# Adafrruit_Bluefruit_LE_USB_Friend_CP2102.net
KiCad netlist of a schematic drawn in EAGLE
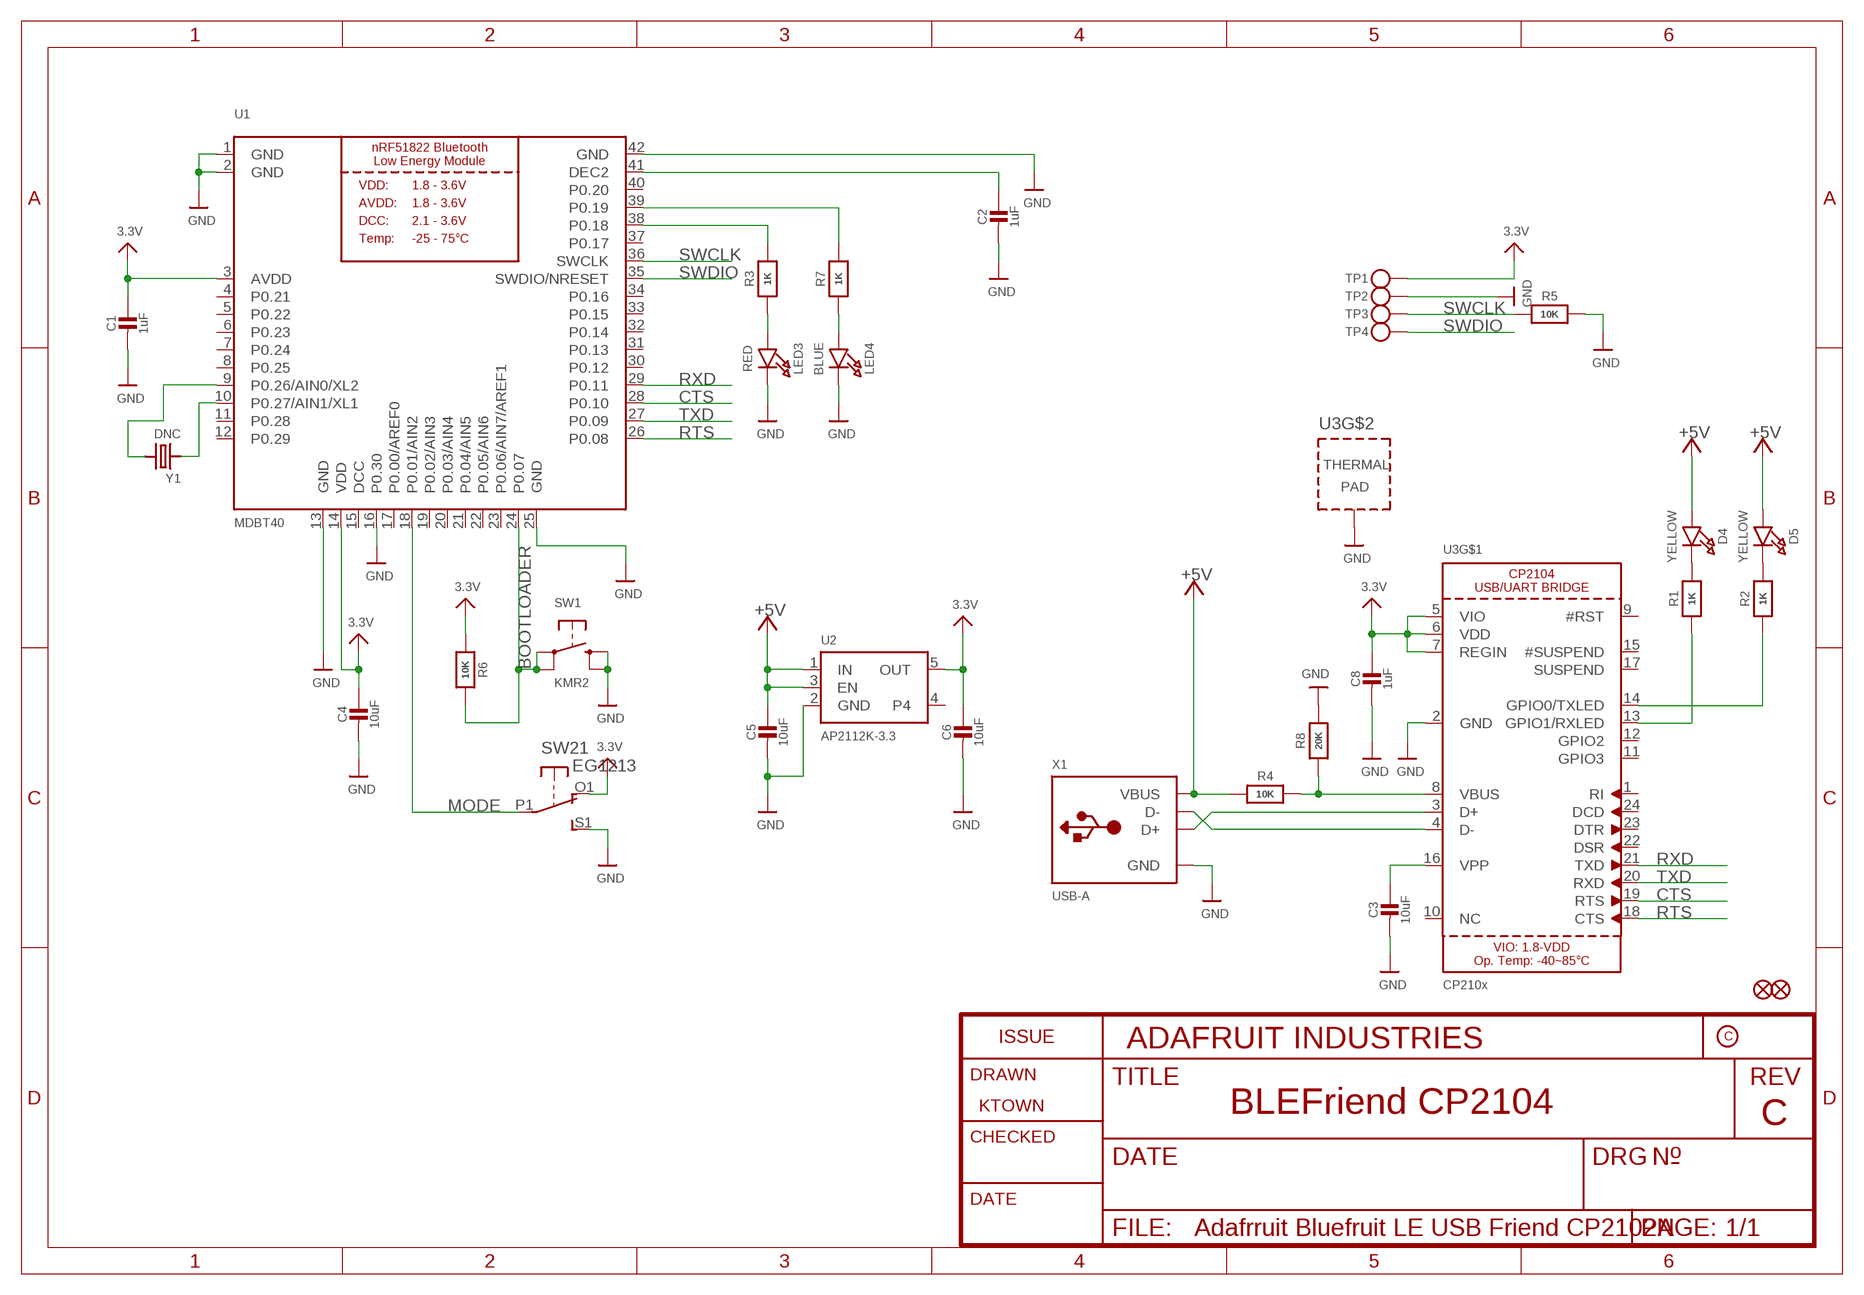
[diagram p0: schematic, sheet 1]

(export (version "E")
  (design (tool "Eeschema 10.0.6"))
  (components
    (comp (ref "C1")
      (value "1uF")
      (footprint "eagle-import:0603-NO")
      (libsource (lib "eagle-import") (part "CAP_CERAMIC0603_NO"))
    )
    (comp (ref "C2")
      (value "1uF")
      (footprint "eagle-import:0603-NO")
      (libsource (lib "eagle-import") (part "CAP_CERAMIC0603_NO"))
    )
    (comp (ref "C3")
      (value "10uF")
      (footprint "eagle-import:0805-NO")
      (libsource (lib "eagle-import") (part "CAP_CERAMIC0805-NOOUTLINE"))
    )
    (comp (ref "C4")
      (value "10uF")
      (footprint "eagle-import:0805-NO")
      (libsource (lib "eagle-import") (part "CAP_CERAMIC0805-NOOUTLINE"))
    )
    (comp (ref "C5")
      (value "10uF")
      (footprint "eagle-import:0805-NO")
      (libsource (lib "eagle-import") (part "CAP_CERAMIC0805-NOOUTLINE"))
    )
    (comp (ref "C6")
      (value "10uF")
      (footprint "eagle-import:0805-NO")
      (libsource (lib "eagle-import") (part "CAP_CERAMIC0805-NOOUTLINE"))
    )
    (comp (ref "C8")
      (value "1uF")
      (footprint "eagle-import:0603-NO")
      (libsource (lib "eagle-import") (part "CAP_CERAMIC0603_NO"))
    )
    (comp (ref "D4")
      (value "YELLOW")
      (footprint "eagle-import:CHIPLED_0805_NOOUTLINE")
      (libsource (lib "eagle-import") (part "LED0805_NOOUTLINE"))
    )
    (comp (ref "D5")
      (value "YELLOW")
      (footprint "eagle-import:CHIPLED_0805_NOOUTLINE")
      (libsource (lib "eagle-import") (part "LED0805_NOOUTLINE"))
    )
    (comp (ref "FID1")
      (value "FIDUCIAL_1MM")
      (footprint "eagle-import:FIDUCIAL_1MM")
      (libsource (lib "eagle-import") (part "FIDUCIAL_1MM"))
    )
    (comp (ref "FID2")
      (value "FIDUCIAL_1MM")
      (footprint "eagle-import:FIDUCIAL_1MM")
      (libsource (lib "eagle-import") (part "FIDUCIAL_1MM"))
    )
    (comp (ref "LED3")
      (value "RED")
      (footprint "eagle-import:CHIPLED_0805_NOOUTLINE")
      (libsource (lib "eagle-import") (part "LED0805_NOOUTLINE"))
    )
    (comp (ref "LED4")
      (value "BLUE")
      (footprint "eagle-import:CHIPLED_0805_NOOUTLINE")
      (libsource (lib "eagle-import") (part "LED0805_NOOUTLINE"))
    )
    (comp (ref "R1")
      (value "1K")
      (footprint "eagle-import:0603-NO")
      (libsource (lib "eagle-import") (part "RESISTOR_0603_NOOUT"))
    )
    (comp (ref "R2")
      (value "1K")
      (footprint "eagle-import:0603-NO")
      (libsource (lib "eagle-import") (part "RESISTOR_0603_NOOUT"))
    )
    (comp (ref "R3")
      (value "1K")
      (footprint "eagle-import:0603-NO")
      (libsource (lib "eagle-import") (part "RESISTOR_0603_NOOUT"))
    )
    (comp (ref "R4")
      (value "10K")
      (footprint "eagle-import:0603-NO")
      (libsource (lib "eagle-import") (part "RESISTOR_0603_NOOUT"))
    )
    (comp (ref "R5")
      (value "10K")
      (footprint "eagle-import:0603-NO")
      (libsource (lib "eagle-import") (part "RESISTOR_0603_NOOUT"))
    )
    (comp (ref "R6")
      (value "10K")
      (footprint "eagle-import:0603-NO")
      (libsource (lib "eagle-import") (part "RESISTOR_0603_NOOUT"))
    )
    (comp (ref "R7")
      (value "1K")
      (footprint "eagle-import:0603-NO")
      (libsource (lib "eagle-import") (part "RESISTOR_0603_NOOUT"))
    )
    (comp (ref "R8")
      (value "20K")
      (footprint "eagle-import:0603-NO")
      (libsource (lib "eagle-import") (part "RESISTOR_0603_NOOUT"))
    )
    (comp (ref "SW1")
      (value "KMR2")
      (footprint "eagle-import:BTN_KMR2_4.6X2.8")
      (libsource (lib "eagle-import") (part "SWITCH_TACT_SMT4.6X2.8"))
    )
    (comp (ref "SW2")
      (value "EG1213")
      (footprint "eagle-import:EG1390")
      (libsource (lib "eagle-import") (part "DPDT-EG1390"))
    )
    (comp (ref "TP1")
      (value "TESTPOINTROUND2MM")
      (footprint "eagle-import:TESTPOINT_ROUND_2MM")
      (libsource (lib "eagle-import") (part "TESTPOINTROUND2MM"))
    )
    (comp (ref "TP2")
      (value "TESTPOINTROUND2MM")
      (footprint "eagle-import:TESTPOINT_ROUND_2MM")
      (libsource (lib "eagle-import") (part "TESTPOINTROUND2MM"))
    )
    (comp (ref "TP3")
      (value "TESTPOINTROUND2MM")
      (footprint "eagle-import:TESTPOINT_ROUND_2MM")
      (libsource (lib "eagle-import") (part "TESTPOINTROUND2MM"))
    )
    (comp (ref "TP4")
      (value "TESTPOINTROUND2MM")
      (footprint "eagle-import:TESTPOINT_ROUND_2MM")
      (libsource (lib "eagle-import") (part "TESTPOINTROUND2MM"))
    )
    (comp (ref "U1")
      (value "MDBT40")
      (footprint "eagle-import:BLE_MODULE_RAYTAC_MDBT40")
      (libsource (lib "eagle-import") (part "NRF51822_MODULE_MDBT40"))
    )
    (comp (ref "U2")
      (value "AP2112K-3.3")
      (footprint "eagle-import:SOT23-5")
      (libsource (lib "eagle-import") (part "VREG_SOT23-5"))
    )
    (comp (ref "U3")
      (value "CP210x")
      (footprint "eagle-import:QFN24_4MM_SMSC")
      (libsource (lib "eagle-import") (part "CP2104"))
    )
    (comp (ref "X1")
      (value "USB-A")
      (footprint "eagle-import:USB_A-THM")
      (libsource (lib "eagle-import") (part "USB_TYPEA_CLIENTTHM"))
    )
    (comp (ref "Y1")
      (value "DNC")
      (footprint "eagle-import:CRYSTAL_CYL_2X6MM_SMT")
      (libsource (lib "eagle-import") (part "CRYSTAL2.0X6.0_32.768"))
    )
  )
  (nets
    (net (code "1") (name "+5V") (class "Default")
      (node (ref "C5") (pin "1") (pinfunction "1_1") (pintype "passive"))
      (node (ref "D4") (pin "A") (pinfunction "A_A") (pintype "passive"))
      (node (ref "D5") (pin "A") (pinfunction "A_A") (pintype "passive"))
      (node (ref "R4") (pin "1") (pinfunction "1_1") (pintype "passive"))
      (node (ref "U2") (pin "1") (pinfunction "IN_1") (pintype "power_in"))
      (node (ref "U2") (pin "3") (pinfunction "EN_3") (pintype "input"))
      (node (ref "X1") (pin "VBUS") (pinfunction "VBUS_VBUS") (pintype "power_in"))
    )
    (net (code "2") (name "/BOOTLOADER") (class "Default")
      (node (ref "R6") (pin "2") (pinfunction "2_2") (pintype "passive"))
      (node (ref "SW1") (pin "A") (pinfunction "P_A") (pintype "passive"))
      (node (ref "SW1") (pin "A'") (pinfunction "P1_A'") (pintype "passive"))
      (node (ref "U1") (pin "24") (pinfunction "P0.07_24") (pintype "bidirectional"))
    )
    (net (code "3") (name "/CTS") (class "Default")
      (node (ref "U1") (pin "28") (pinfunction "P0.10_28") (pintype "bidirectional"))
      (node (ref "U3") (pin "19") (pinfunction "RTS_19") (pintype "output"))
    )
    (net (code "4") (name "/DCC") (class "Default")
      (node (ref "U1") (pin "15") (pinfunction "DCC_15") (pintype "power_in"))
    )
    (net (code "5") (name "/MODE") (class "Default")
      (node (ref "SW2") (pin "P1") (pinfunction "P_P1") (pintype "passive"))
      (node (ref "U1") (pin "18") (pinfunction "P0.01/AIN2_18") (pintype "bidirectional"))
    )
    (net (code "6") (name "/RTS") (class "Default")
      (node (ref "U1") (pin "26") (pinfunction "P0.08_26") (pintype "bidirectional"))
      (node (ref "U3") (pin "18") (pinfunction "CTS_18") (pintype "input"))
    )
    (net (code "7") (name "/RXD") (class "Default")
      (node (ref "U1") (pin "29") (pinfunction "P0.11_29") (pintype "bidirectional"))
      (node (ref "U3") (pin "21") (pinfunction "TXD_21") (pintype "output"))
    )
    (net (code "8") (name "/SWCLK") (class "Default")
      (node (ref "R5") (pin "1") (pinfunction "1_1") (pintype "passive"))
      (node (ref "TP3") (pin "P$1") (pinfunction "P$1_P$1") (pintype "bidirectional"))
      (node (ref "U1") (pin "36") (pinfunction "SWCLK_36") (pintype "bidirectional"))
    )
    (net (code "9") (name "/SWDIO") (class "Default")
      (node (ref "TP4") (pin "P$1") (pinfunction "P$1_P$1") (pintype "bidirectional"))
      (node (ref "U1") (pin "35") (pinfunction "SWDIO/NRESET_35") (pintype "bidirectional"))
    )
    (net (code "10") (name "/TXD") (class "Default")
      (node (ref "U1") (pin "27") (pinfunction "P0.09_27") (pintype "bidirectional"))
      (node (ref "U3") (pin "20") (pinfunction "RXD_20") (pintype "input"))
    )
    (net (code "11") (name "3.3V") (class "Default")
      (node (ref "C1") (pin "1") (pinfunction "1_1") (pintype "passive"))
      (node (ref "C4") (pin "1") (pinfunction "1_1") (pintype "passive"))
      (node (ref "C6") (pin "1") (pinfunction "1_1") (pintype "passive"))
      (node (ref "C8") (pin "1") (pinfunction "1_1") (pintype "passive"))
      (node (ref "R6") (pin "1") (pinfunction "1_1") (pintype "passive"))
      (node (ref "SW2") (pin "O1") (pinfunction "O_O1") (pintype "passive"))
      (node (ref "TP1") (pin "P$1") (pinfunction "P$1_P$1") (pintype "bidirectional"))
      (node (ref "U1") (pin "14") (pinfunction "VDD_14") (pintype "power_in"))
      (node (ref "U1") (pin "3") (pinfunction "AVDD_3") (pintype "power_in"))
      (node (ref "U2") (pin "5") (pinfunction "OUT_5") (pintype "power_in"))
      (node (ref "U3") (pin "5") (pinfunction "VIO_5") (pintype "power_in"))
      (node (ref "U3") (pin "6") (pinfunction "VDD_6") (pintype "power_in"))
      (node (ref "U3") (pin "7") (pinfunction "REGIN_7") (pintype "power_in"))
    )
    (net (code "12") (name "GND") (class "Default")
      (node (ref "C1") (pin "2") (pinfunction "2_2") (pintype "passive"))
      (node (ref "C2") (pin "2") (pinfunction "2_2") (pintype "passive"))
      (node (ref "C3") (pin "2") (pinfunction "2_2") (pintype "passive"))
      (node (ref "C4") (pin "2") (pinfunction "2_2") (pintype "passive"))
      (node (ref "C5") (pin "2") (pinfunction "2_2") (pintype "passive"))
      (node (ref "C6") (pin "2") (pinfunction "2_2") (pintype "passive"))
      (node (ref "C8") (pin "2") (pinfunction "2_2") (pintype "passive"))
      (node (ref "LED3") (pin "C") (pinfunction "C_C") (pintype "passive"))
      (node (ref "LED4") (pin "C") (pinfunction "C_C") (pintype "passive"))
      (node (ref "R5") (pin "2") (pinfunction "2_2") (pintype "passive"))
      (node (ref "R8") (pin "2") (pinfunction "2_2") (pintype "passive"))
      (node (ref "SW1") (pin "B") (pinfunction "S_B") (pintype "passive"))
      (node (ref "SW1") (pin "B'") (pinfunction "S1_B'") (pintype "passive"))
      (node (ref "SW2") (pin "S1") (pinfunction "S_S1") (pintype "passive"))
      (node (ref "TP2") (pin "P$1") (pinfunction "P$1_P$1") (pintype "bidirectional"))
      (node (ref "U1") (pin "1") (pinfunction "GND_1") (pintype "power_in"))
      (node (ref "U1") (pin "13") (pinfunction "GND_13") (pintype "power_in"))
      (node (ref "U1") (pin "16") (pinfunction "P0.30_16") (pintype "bidirectional"))
      (node (ref "U1") (pin "2") (pinfunction "GND_2") (pintype "power_in"))
      (node (ref "U1") (pin "25") (pinfunction "GND_25") (pintype "power_in"))
      (node (ref "U1") (pin "42") (pinfunction "GND_42") (pintype "power_in"))
      (node (ref "U2") (pin "2") (pinfunction "GND_2") (pintype "power_in"))
      (node (ref "U3") (pin "2") (pinfunction "GND_2") (pintype "power_in"))
      (node (ref "U3") (pin "THERM") (pinfunction "TP_THERM") (pintype "power_in"))
      (node (ref "X1") (pin "GND") (pinfunction "GND_GND") (pintype "power_in"))
    )
    (net (code "13") (name "Net-(D4-PadC)") (class "Default")
      (node (ref "D4") (pin "C") (pinfunction "C_C") (pintype "passive"))
      (node (ref "R1") (pin "2") (pinfunction "2_2") (pintype "passive"))
    )
    (net (code "14") (name "Net-(D5-PadC)") (class "Default")
      (node (ref "D5") (pin "C") (pinfunction "C_C") (pintype "passive"))
      (node (ref "R2") (pin "2") (pinfunction "2_2") (pintype "passive"))
    )
    (net (code "15") (name "Net-(LED3-PadA)") (class "Default")
      (node (ref "LED3") (pin "A") (pinfunction "A_A") (pintype "passive"))
      (node (ref "R3") (pin "1") (pinfunction "1_1") (pintype "passive"))
    )
    (net (code "16") (name "Net-(LED4-PadA)") (class "Default")
      (node (ref "LED4") (pin "A") (pinfunction "A_A") (pintype "passive"))
      (node (ref "R7") (pin "1") (pinfunction "1_1") (pintype "passive"))
    )
    (net (code "17") (name "Net-(U1-DEC2)") (class "Default")
      (node (ref "C2") (pin "1") (pinfunction "1_1") (pintype "passive"))
      (node (ref "U1") (pin "41") (pinfunction "DEC2_41") (pintype "power_in"))
    )
    (net (code "18") (name "Net-(U1-P0.18)") (class "Default")
      (node (ref "R3") (pin "2") (pinfunction "2_2") (pintype "passive"))
      (node (ref "U1") (pin "38") (pinfunction "P0.18_38") (pintype "bidirectional"))
    )
    (net (code "19") (name "Net-(U1-P0.19)") (class "Default")
      (node (ref "R7") (pin "2") (pinfunction "2_2") (pintype "passive"))
      (node (ref "U1") (pin "39") (pinfunction "P0.19_39") (pintype "bidirectional"))
    )
    (net (code "20") (name "Net-(U1-P0.26{slash}AIN0{slash}XL2)") (class "Default")
      (node (ref "U1") (pin "9") (pinfunction "P0.26/AIN0/XL2_9") (pintype "bidirectional"))
      (node (ref "Y1") (pin "2") (pinfunction "2_2") (pintype "passive"))
    )
    (net (code "21") (name "Net-(U1-P0.27{slash}AIN1{slash}XL1)") (class "Default")
      (node (ref "U1") (pin "10") (pinfunction "P0.27/AIN1/XL1_10") (pintype "bidirectional"))
      (node (ref "Y1") (pin "1") (pinfunction "1_1") (pintype "passive"))
    )
    (net (code "22") (name "Net-(U3A-D+)") (class "Default")
      (node (ref "U3") (pin "3") (pinfunction "D+_3") (pintype "bidirectional"))
      (node (ref "X1") (pin "D+") (pinfunction "D+_D+") (pintype "bidirectional"))
    )
    (net (code "23") (name "Net-(U3A-D-)") (class "Default")
      (node (ref "U3") (pin "4") (pinfunction "D-_4") (pintype "bidirectional"))
      (node (ref "X1") (pin "D-") (pinfunction "D-_D-") (pintype "bidirectional"))
    )
    (net (code "24") (name "Net-(U3A-GPIO0{slash}TXLED)") (class "Default")
      (node (ref "R2") (pin "1") (pinfunction "1_1") (pintype "passive"))
      (node (ref "U3") (pin "14") (pinfunction "GPIO0/TXLED_14") (pintype "bidirectional"))
    )
    (net (code "25") (name "Net-(U3A-GPIO1{slash}RXLED)") (class "Default")
      (node (ref "R1") (pin "1") (pinfunction "1_1") (pintype "passive"))
      (node (ref "U3") (pin "13") (pinfunction "GPIO1/RXLED_13") (pintype "bidirectional"))
    )
    (net (code "26") (name "Net-(U3A-VBUS)") (class "Default")
      (node (ref "R4") (pin "2") (pinfunction "2_2") (pintype "passive"))
      (node (ref "R8") (pin "1") (pinfunction "1_1") (pintype "passive"))
      (node (ref "U3") (pin "8") (pinfunction "VBUS_8") (pintype "power_in"))
    )
    (net (code "27") (name "Net-(U3A-VPP)") (class "Default")
      (node (ref "C3") (pin "1") (pinfunction "1_1") (pintype "passive"))
      (node (ref "U3") (pin "16") (pinfunction "VPP_16") (pintype "bidirectional"))
    )
    (net (code "28") (name "unconnected-(U1-P0.00{slash}AREF0-Pad17)") (class "Default")
      (node (ref "U1") (pin "17") (pinfunction "P0.00/AREF0_17") (pintype "bidirectional"))
    )
    (net (code "29") (name "unconnected-(U1-P0.02{slash}AIN3-Pad19)") (class "Default")
      (node (ref "U1") (pin "19") (pinfunction "P0.02/AIN3_19") (pintype "bidirectional"))
    )
    (net (code "30") (name "unconnected-(U1-P0.03{slash}AIN4-Pad20)") (class "Default")
      (node (ref "U1") (pin "20") (pinfunction "P0.03/AIN4_20") (pintype "bidirectional"))
    )
    (net (code "31") (name "unconnected-(U1-P0.04{slash}AIN5-Pad21)") (class "Default")
      (node (ref "U1") (pin "21") (pinfunction "P0.04/AIN5_21") (pintype "bidirectional"))
    )
    (net (code "32") (name "unconnected-(U1-P0.05{slash}AIN6-Pad22)") (class "Default")
      (node (ref "U1") (pin "22") (pinfunction "P0.05/AIN6_22") (pintype "bidirectional"))
    )
    (net (code "33") (name "unconnected-(U1-P0.06{slash}AIN7{slash}AREF1-Pad23)") (class "Default")
      (node (ref "U1") (pin "23") (pinfunction "P0.06/AIN7/AREF1_23") (pintype "bidirectional"))
    )
    (net (code "34") (name "unconnected-(U1-P0.12-Pad30)") (class "Default")
      (node (ref "U1") (pin "30") (pinfunction "P0.12_30") (pintype "bidirectional"))
    )
    (net (code "35") (name "unconnected-(U1-P0.13-Pad31)") (class "Default")
      (node (ref "U1") (pin "31") (pinfunction "P0.13_31") (pintype "bidirectional"))
    )
    (net (code "36") (name "unconnected-(U1-P0.14-Pad32)") (class "Default")
      (node (ref "U1") (pin "32") (pinfunction "P0.14_32") (pintype "bidirectional"))
    )
    (net (code "37") (name "unconnected-(U1-P0.15-Pad33)") (class "Default")
      (node (ref "U1") (pin "33") (pinfunction "P0.15_33") (pintype "bidirectional"))
    )
    (net (code "38") (name "unconnected-(U1-P0.16-Pad34)") (class "Default")
      (node (ref "U1") (pin "34") (pinfunction "P0.16_34") (pintype "bidirectional"))
    )
    (net (code "39") (name "unconnected-(U1-P0.17-Pad37)") (class "Default")
      (node (ref "U1") (pin "37") (pinfunction "P0.17_37") (pintype "bidirectional"))
    )
    (net (code "40") (name "unconnected-(U1-P0.20-Pad40)") (class "Default")
      (node (ref "U1") (pin "40") (pinfunction "P0.20_40") (pintype "bidirectional"))
    )
    (net (code "41") (name "unconnected-(U1-P0.21-Pad4)") (class "Default")
      (node (ref "U1") (pin "4") (pinfunction "P0.21_4") (pintype "bidirectional"))
    )
    (net (code "42") (name "unconnected-(U1-P0.22-Pad5)") (class "Default")
      (node (ref "U1") (pin "5") (pinfunction "P0.22_5") (pintype "bidirectional"))
    )
    (net (code "43") (name "unconnected-(U1-P0.23-Pad6)") (class "Default")
      (node (ref "U1") (pin "6") (pinfunction "P0.23_6") (pintype "bidirectional"))
    )
    (net (code "44") (name "unconnected-(U1-P0.24-Pad7)") (class "Default")
      (node (ref "U1") (pin "7") (pinfunction "P0.24_7") (pintype "bidirectional"))
    )
    (net (code "45") (name "unconnected-(U1-P0.25-Pad8)") (class "Default")
      (node (ref "U1") (pin "8") (pinfunction "P0.25_8") (pintype "bidirectional"))
    )
    (net (code "46") (name "unconnected-(U1-P0.28-Pad11)") (class "Default")
      (node (ref "U1") (pin "11") (pinfunction "P0.28_11") (pintype "bidirectional"))
    )
    (net (code "47") (name "unconnected-(U1-P0.29-Pad12)") (class "Default")
      (node (ref "U1") (pin "12") (pinfunction "P0.29_12") (pintype "bidirectional"))
    )
    (net (code "48") (name "unconnected-(U2-P4-Pad4)") (class "Default")
      (node (ref "U2") (pin "4") (pinfunction "P4_4") (pintype "bidirectional"))
    )
    (net (code "49") (name "unconnected-(U3A-#RST-Pad9)") (class "Default")
      (node (ref "U3") (pin "9") (pinfunction "#RST_9") (pintype "bidirectional"))
    )
    (net (code "50") (name "unconnected-(U3A-#SUSPEND-Pad15)") (class "Default")
      (node (ref "U3") (pin "15") (pinfunction "#SUSPEND_15") (pintype "output"))
    )
    (net (code "51") (name "unconnected-(U3A-DCD-Pad24)") (class "Default")
      (node (ref "U3") (pin "24") (pinfunction "DCD_24") (pintype "input"))
    )
    (net (code "52") (name "unconnected-(U3A-DSR-Pad22)") (class "Default")
      (node (ref "U3") (pin "22") (pinfunction "DSR_22") (pintype "input"))
    )
    (net (code "53") (name "unconnected-(U3A-DTR-Pad23)") (class "Default")
      (node (ref "U3") (pin "23") (pinfunction "DTR_23") (pintype "output"))
    )
    (net (code "54") (name "unconnected-(U3A-GPIO2-Pad12)") (class "Default")
      (node (ref "U3") (pin "12") (pinfunction "GPIO2_12") (pintype "bidirectional"))
    )
    (net (code "55") (name "unconnected-(U3A-GPIO3-Pad11)") (class "Default")
      (node (ref "U3") (pin "11") (pinfunction "GPIO3_11") (pintype "bidirectional"))
    )
    (net (code "56") (name "unconnected-(U3A-NC-Pad10)") (class "Default")
      (node (ref "U3") (pin "10") (pinfunction "NC_10") (pintype "no_connect"))
    )
    (net (code "57") (name "unconnected-(U3A-RI-Pad1)") (class "Default")
      (node (ref "U3") (pin "1") (pinfunction "RI_1") (pintype "input"))
    )
    (net (code "58") (name "unconnected-(U3A-SUSPEND-Pad17)") (class "Default")
      (node (ref "U3") (pin "17") (pinfunction "SUSPEND_17") (pintype "output"))
    )
  )
)
